# NEpic.net
KiCad netlist of a schematic drawn in Altium Designer
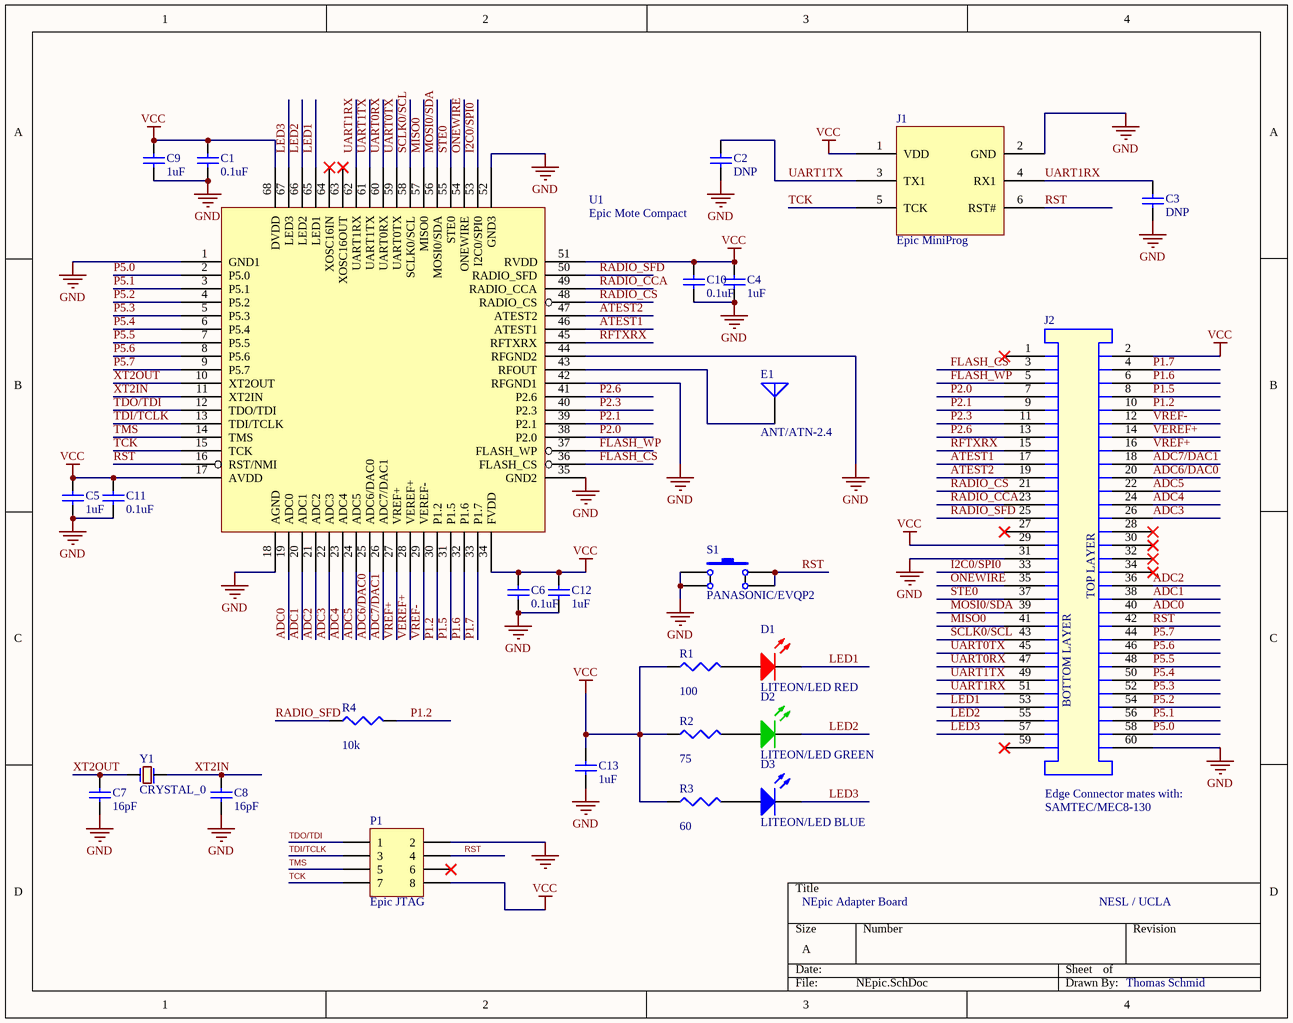
[diagram p0: NEpic.SchDoc]

(export (version "E")
  (design (tool "Eeschema 10.0.6"))
  (components
    (comp (ref "C1")
      (value "0.1uF")
      (footprint "CC1608-0603")
      (description "Capacitor (Semiconductor SIM Model)")
      (fields (field (name "Comment") "Cap") (field (name "PUBLISHER") "Altium Limited"))
      (libsource (lib "Thomas") (part "Cap"))
    )
    (comp (ref "C2")
      (value "DNP")
      (footprint "CC1608-0603")
      (description "Capacitor (Semiconductor SIM Model)")
      (fields (field (name "Comment") "Cap") (field (name "PUBLISHER") "Altium Limited"))
      (libsource (lib "Thomas") (part "Cap"))
    )
    (comp (ref "C3")
      (value "DNP")
      (footprint "CC1608-0603")
      (description "Capacitor (Semiconductor SIM Model)")
      (fields (field (name "Comment") "Cap") (field (name "PUBLISHER") "Altium Limited"))
      (libsource (lib "Thomas") (part "Cap"))
    )
    (comp (ref "C4")
      (value "1uF")
      (footprint "CC1608-0603")
      (description "Capacitor (Semiconductor SIM Model)")
      (fields (field (name "Comment") "Cap") (field (name "PUBLISHER") "Altium Limited"))
      (libsource (lib "Thomas") (part "Cap"))
    )
    (comp (ref "C5")
      (value "1uF")
      (footprint "CC1608-0603")
      (description "Capacitor (Semiconductor SIM Model)")
      (fields (field (name "Comment") "Cap") (field (name "PUBLISHER") "Altium Limited"))
      (libsource (lib "Thomas") (part "Cap"))
    )
    (comp (ref "C6")
      (value "0.1uF")
      (footprint "CC1608-0603")
      (description "Capacitor (Semiconductor SIM Model)")
      (fields (field (name "Comment") "Cap") (field (name "PUBLISHER") "Altium Limited"))
      (libsource (lib "Thomas") (part "Cap"))
    )
    (comp (ref "C7")
      (value "16pF")
      (footprint "CC1608-0603")
      (description "Capacitor (Semiconductor SIM Model)")
      (fields (field (name "Comment") "Cap") (field (name "PUBLISHER") "Altium Limited"))
      (libsource (lib "Thomas") (part "Cap"))
    )
    (comp (ref "C8")
      (value "16pF")
      (footprint "CC1608-0603")
      (description "Capacitor (Semiconductor SIM Model)")
      (fields (field (name "Comment") "Cap") (field (name "PUBLISHER") "Altium Limited"))
      (libsource (lib "Thomas") (part "Cap"))
    )
    (comp (ref "C9")
      (value "1uF")
      (footprint "CC1608-0603")
      (description "Capacitor (Semiconductor SIM Model)")
      (fields (field (name "Comment") "Cap") (field (name "PUBLISHER") "Altium Limited"))
      (libsource (lib "Thomas") (part "Cap"))
    )
    (comp (ref "C10")
      (value "0.1uF")
      (footprint "CC1608-0603")
      (description "Capacitor (Semiconductor SIM Model)")
      (fields (field (name "Comment") "Cap") (field (name "PUBLISHER") "Altium Limited"))
      (libsource (lib "Thomas") (part "Cap"))
    )
    (comp (ref "C11")
      (value "0.1uF")
      (footprint "CC1608-0603")
      (description "Capacitor (Semiconductor SIM Model)")
      (fields (field (name "Comment") "Cap") (field (name "PUBLISHER") "Altium Limited"))
      (libsource (lib "Thomas") (part "Cap"))
    )
    (comp (ref "C12")
      (value "1uF")
      (footprint "CC1608-0603")
      (description "Capacitor (Semiconductor SIM Model)")
      (fields (field (name "Comment") "Cap") (field (name "PUBLISHER") "Altium Limited"))
      (libsource (lib "Thomas") (part "Cap"))
    )
    (comp (ref "C13")
      (value "1uF")
      (footprint "CC1608-0603")
      (description "Capacitor (Semiconductor SIM Model)")
      (fields (field (name "Comment") "Cap") (field (name "PUBLISHER") "Altium Limited"))
      (libsource (lib "Thomas") (part "Cap"))
    )
    (comp (ref "D1")
      (value "LITEON/LED RED")
      (footprint "LITEON/LED/0603")
      (description "LiteOn Red LED 0605 Footprint")
      (fields (field (name "PUBLISHER") "Altium Limited"))
      (libsource (lib "Thomas") (part "LITEON/LED RED"))
    )
    (comp (ref "D2")
      (value "LITEON/LED GREEN")
      (footprint "LITEON/LED/0603")
      (description "LiteOn Green LED 0605 Footprint")
      (fields (field (name "PUBLISHER") "Altium Limited"))
      (libsource (lib "Thomas") (part "LITEON/LED GREEN"))
    )
    (comp (ref "D3")
      (value "LITEON/LED BLUE")
      (footprint "LITEON/LED/0603")
      (description "LiteOn Blue LED 0605 Footprint")
      (fields (field (name "PUBLISHER") "Altium Limited"))
      (libsource (lib "Thomas") (part "LITEON/LED BLUE"))
    )
    (comp (ref "E1")
      (value "ANT/ATN-2.4")
      (footprint "ANT/ANT-2.45-CHPCT-ND")
      (description "ANT/ANT-2.4 Chip Antenna")
      (fields (field (name "PUBLISHER") "Altium Limited"))
      (libsource (lib "Thomas") (part "Antenna"))
    )
    (comp (ref "J1")
      (value "Epic MiniProg")
      (footprint "6-pin 2mm")
      (libsource (lib "Thomas") (part "Epic MiniProg"))
    )
    (comp (ref "J2")
      (value "SAMTEC/MEC8-130")
      (footprint "SAMTEC/MEC8L-130-CARD")
      (description "0.8mm Pitch 60 pin Card Edge Socket")
      (libsource (lib "Thomas") (part "SAMTEC/HSEC8/50"))
    )
    (comp (ref "P1")
      (value "Epic JTAG")
      (footprint "Thomas/Header 2x4 2mm")
      (description "Header, 4-Pin, Dual row")
      (fields (field (name "PUBLISHER") "Altium Limited"))
      (libsource (lib "Miscellaneous Connectors") (part "Header 4X2"))
    )
    (comp (ref "R1")
      (value "100")
      (footprint "CR1608-0603")
      (description "Resistor")
      (fields (field (name "Comment") "Res3") (field (name "PUBLISHER") "Altium Limited"))
      (libsource (lib "Miscellaneous Devices") (part "Res3"))
    )
    (comp (ref "R2")
      (value "75")
      (footprint "CR1608-0603")
      (description "Resistor")
      (fields (field (name "Comment") "Res3") (field (name "PUBLISHER") "Altium Limited"))
      (libsource (lib "Miscellaneous Devices") (part "Res3"))
    )
    (comp (ref "R3")
      (value "60")
      (footprint "CR1608-0603")
      (description "Resistor")
      (fields (field (name "Comment") "Res3") (field (name "PUBLISHER") "Altium Limited"))
      (libsource (lib "Miscellaneous Devices") (part "Res3"))
    )
    (comp (ref "R4")
      (value "10k")
      (footprint "CR1608-0603")
      (description "Resistor")
      (fields (field (name "Comment") "Res3") (field (name "PUBLISHER") "Altium Limited"))
      (libsource (lib "Miscellaneous Devices") (part "Res3"))
    )
    (comp (ref "S1")
      (value "PANASONIC/EVQP2")
      (footprint "PANASONIC/EVQP2")
      (fields (field (name "PUBLISHER") "Altium Limited"))
      (libsource (lib "Thomas") (part "PANASONIC/EVQP2"))
    )
    (comp (ref "U1")
      (value "Epic Mote Compact")
      (footprint "EPIC-Footprint")
      (libsource (lib "Thomas") (part "Epic Mote Compact"))
    )
    (comp (ref "Y1")
      (value "CRYSTAL_0")
      (footprint "FOX/FQ7050B")
      (libsource (lib "Thomas") (part "CRYSTAL_0"))
    )
  )
  (nets
    (net (code "1") (name "/ADC0") (class "Default")
      (node (ref "J2") (pin "40") (pinfunction "40_40") (pintype "passive"))
      (node (ref "U1") (pin "19") (pinfunction "ADC0_19") (pintype "passive"))
    )
    (net (code "2") (name "/ADC1") (class "Default")
      (node (ref "J2") (pin "38") (pinfunction "38_38") (pintype "passive"))
      (node (ref "U1") (pin "20") (pinfunction "ADC1_20") (pintype "passive"))
    )
    (net (code "3") (name "/ADC2") (class "Default")
      (node (ref "J2") (pin "36") (pinfunction "36_36") (pintype "passive"))
      (node (ref "U1") (pin "21") (pinfunction "ADC2_21") (pintype "passive"))
    )
    (net (code "4") (name "/ADC3") (class "Default")
      (node (ref "J2") (pin "26") (pinfunction "26_26") (pintype "passive"))
      (node (ref "U1") (pin "22") (pinfunction "ADC3_22") (pintype "passive"))
    )
    (net (code "5") (name "/ADC4") (class "Default")
      (node (ref "J2") (pin "24") (pinfunction "24_24") (pintype "passive"))
      (node (ref "U1") (pin "23") (pinfunction "ADC4_23") (pintype "passive"))
    )
    (net (code "6") (name "/ADC5") (class "Default")
      (node (ref "J2") (pin "22") (pinfunction "22_22") (pintype "passive"))
      (node (ref "U1") (pin "24") (pinfunction "ADC5_24") (pintype "passive"))
    )
    (net (code "7") (name "/ADC6{slash}DAC0") (class "Default")
      (node (ref "J2") (pin "20") (pinfunction "20_20") (pintype "passive"))
      (node (ref "U1") (pin "25") (pinfunction "ADC6/DAC0_25") (pintype "passive"))
    )
    (net (code "8") (name "/ADC7{slash}DAC1") (class "Default")
      (node (ref "J2") (pin "18") (pinfunction "18_18") (pintype "passive"))
      (node (ref "U1") (pin "26") (pinfunction "ADC7/DAC1_26") (pintype "passive"))
    )
    (net (code "9") (name "/ATEST1") (class "Default")
      (node (ref "J2") (pin "17") (pinfunction "17_17") (pintype "passive"))
      (node (ref "U1") (pin "46") (pinfunction "ATEST1_46") (pintype "passive"))
    )
    (net (code "10") (name "/ATEST2") (class "Default")
      (node (ref "J2") (pin "19") (pinfunction "19_19") (pintype "passive"))
      (node (ref "U1") (pin "47") (pinfunction "ATEST2_47") (pintype "passive"))
    )
    (net (code "11") (name "/FLASH_CS") (class "Default")
      (node (ref "J2") (pin "3") (pinfunction "3_3") (pintype "passive"))
      (node (ref "U1") (pin "36") (pinfunction "FLASH_CS_36") (pintype "passive"))
    )
    (net (code "12") (name "/FLASH_WP") (class "Default")
      (node (ref "J2") (pin "5") (pinfunction "5_5") (pintype "passive"))
      (node (ref "U1") (pin "37") (pinfunction "FLASH_WP_37") (pintype "passive"))
    )
    (net (code "13") (name "/I2C0{slash}SPI0") (class "Default")
      (node (ref "J2") (pin "33") (pinfunction "33_33") (pintype "passive"))
      (node (ref "U1") (pin "53") (pinfunction "I2C0/SPI0_53") (pintype "passive"))
    )
    (net (code "14") (name "/LED1") (class "Default")
      (node (ref "D1") (pin "2") (pinfunction "K_2") (pintype "passive"))
      (node (ref "J2") (pin "53") (pinfunction "53_53") (pintype "passive"))
      (node (ref "U1") (pin "65") (pinfunction "LED1_65") (pintype "passive"))
    )
    (net (code "15") (name "/LED2") (class "Default")
      (node (ref "D2") (pin "2") (pinfunction "K_2") (pintype "passive"))
      (node (ref "J2") (pin "55") (pinfunction "55_55") (pintype "passive"))
      (node (ref "U1") (pin "66") (pinfunction "LED2_66") (pintype "passive"))
    )
    (net (code "16") (name "/LED3") (class "Default")
      (node (ref "D3") (pin "2") (pinfunction "K_2") (pintype "passive"))
      (node (ref "J2") (pin "57") (pinfunction "57_57") (pintype "passive"))
      (node (ref "U1") (pin "67") (pinfunction "LED3_67") (pintype "passive"))
    )
    (net (code "17") (name "/MISO0") (class "Default")
      (node (ref "J2") (pin "41") (pinfunction "41_41") (pintype "passive"))
      (node (ref "U1") (pin "57") (pinfunction "MISO0_57") (pintype "passive"))
    )
    (net (code "18") (name "/MOSI0{slash}SDA") (class "Default")
      (node (ref "J2") (pin "39") (pinfunction "39_39") (pintype "passive"))
      (node (ref "U1") (pin "56") (pinfunction "MOSI0/SDA_56") (pintype "passive"))
    )
    (net (code "19") (name "/ONEWIRE") (class "Default")
      (node (ref "J2") (pin "35") (pinfunction "35_35") (pintype "passive"))
      (node (ref "U1") (pin "54") (pinfunction "ONEWIRE_54") (pintype "passive"))
    )
    (net (code "20") (name "/P1.2") (class "Default")
      (node (ref "J2") (pin "10") (pinfunction "10_10") (pintype "passive"))
      (node (ref "R4") (pin "2") (pinfunction "2_2") (pintype "passive"))
      (node (ref "U1") (pin "30") (pinfunction "P1.2_30") (pintype "passive"))
    )
    (net (code "21") (name "/P1.5") (class "Default")
      (node (ref "J2") (pin "8") (pinfunction "8_8") (pintype "passive"))
      (node (ref "U1") (pin "31") (pinfunction "P1.5_31") (pintype "passive"))
    )
    (net (code "22") (name "/P1.6") (class "Default")
      (node (ref "J2") (pin "6") (pinfunction "6_6") (pintype "passive"))
      (node (ref "U1") (pin "32") (pinfunction "P1.6_32") (pintype "passive"))
    )
    (net (code "23") (name "/P1.7") (class "Default")
      (node (ref "J2") (pin "4") (pinfunction "4_4") (pintype "passive"))
      (node (ref "U1") (pin "33") (pinfunction "P1.7_33") (pintype "passive"))
    )
    (net (code "24") (name "/P2.0") (class "Default")
      (node (ref "J2") (pin "7") (pinfunction "7_7") (pintype "passive"))
      (node (ref "U1") (pin "38") (pinfunction "P2.0_38") (pintype "passive"))
    )
    (net (code "25") (name "/P2.1") (class "Default")
      (node (ref "J2") (pin "9") (pinfunction "9_9") (pintype "passive"))
      (node (ref "U1") (pin "39") (pinfunction "P2.1_39") (pintype "passive"))
    )
    (net (code "26") (name "/P2.3") (class "Default")
      (node (ref "J2") (pin "11") (pinfunction "11_11") (pintype "passive"))
      (node (ref "U1") (pin "40") (pinfunction "P2.3_40") (pintype "passive"))
    )
    (net (code "27") (name "/P2.6") (class "Default")
      (node (ref "J2") (pin "13") (pinfunction "13_13") (pintype "passive"))
      (node (ref "U1") (pin "41") (pinfunction "P2.6_41") (pintype "passive"))
    )
    (net (code "28") (name "/P5.0") (class "Default")
      (node (ref "J2") (pin "58") (pinfunction "58_58") (pintype "passive"))
      (node (ref "U1") (pin "2") (pinfunction "P5.0_2") (pintype "passive"))
    )
    (net (code "29") (name "/P5.1") (class "Default")
      (node (ref "J2") (pin "56") (pinfunction "56_56") (pintype "passive"))
      (node (ref "U1") (pin "3") (pinfunction "P5.1_3") (pintype "passive"))
    )
    (net (code "30") (name "/P5.2") (class "Default")
      (node (ref "J2") (pin "54") (pinfunction "54_54") (pintype "passive"))
      (node (ref "U1") (pin "4") (pinfunction "P5.2_4") (pintype "passive"))
    )
    (net (code "31") (name "/P5.3") (class "Default")
      (node (ref "J2") (pin "52") (pinfunction "52_52") (pintype "passive"))
      (node (ref "U1") (pin "5") (pinfunction "P5.3_5") (pintype "passive"))
    )
    (net (code "32") (name "/P5.4") (class "Default")
      (node (ref "J2") (pin "50") (pinfunction "50_50") (pintype "passive"))
      (node (ref "U1") (pin "6") (pinfunction "P5.4_6") (pintype "passive"))
    )
    (net (code "33") (name "/P5.5") (class "Default")
      (node (ref "J2") (pin "48") (pinfunction "48_48") (pintype "passive"))
      (node (ref "U1") (pin "7") (pinfunction "P5.5_7") (pintype "passive"))
    )
    (net (code "34") (name "/P5.6") (class "Default")
      (node (ref "J2") (pin "46") (pinfunction "46_46") (pintype "passive"))
      (node (ref "U1") (pin "8") (pinfunction "P5.6_8") (pintype "passive"))
    )
    (net (code "35") (name "/P5.7") (class "Default")
      (node (ref "J2") (pin "44") (pinfunction "44_44") (pintype "passive"))
      (node (ref "U1") (pin "9") (pinfunction "P5.7_9") (pintype "passive"))
    )
    (net (code "36") (name "/RADIO_CCA") (class "Default")
      (node (ref "J2") (pin "23") (pinfunction "23_23") (pintype "passive"))
      (node (ref "U1") (pin "49") (pinfunction "RADIO_CCA_49") (pintype "passive"))
    )
    (net (code "37") (name "/RADIO_CS") (class "Default")
      (node (ref "J2") (pin "21") (pinfunction "21_21") (pintype "passive"))
      (node (ref "U1") (pin "48") (pinfunction "RADIO_CS_48") (pintype "passive"))
    )
    (net (code "38") (name "/RADIO_SFD") (class "Default")
      (node (ref "J2") (pin "25") (pinfunction "25_25") (pintype "passive"))
      (node (ref "R4") (pin "1") (pinfunction "1_1") (pintype "passive"))
      (node (ref "U1") (pin "50") (pinfunction "RADIO_SFD_50") (pintype "passive"))
    )
    (net (code "39") (name "/RFTXRX") (class "Default")
      (node (ref "J2") (pin "15") (pinfunction "15_15") (pintype "passive"))
      (node (ref "U1") (pin "45") (pinfunction "RFTXRX_45") (pintype "passive"))
    )
    (net (code "40") (name "/RST") (class "Default")
      (node (ref "J1") (pin "6") (pinfunction "RST#_6") (pintype "passive"))
      (node (ref "J2") (pin "42") (pinfunction "42_42") (pintype "passive"))
      (node (ref "P1") (pin "4") (pinfunction "4_4") (pintype "passive"))
      (node (ref "S1") (pin "2") (pinfunction "2_2") (pintype "passive"))
      (node (ref "S1") (pin "4") (pinfunction "4_4") (pintype "passive"))
      (node (ref "U1") (pin "16") (pinfunction "RST/NMI_16") (pintype "passive"))
    )
    (net (code "41") (name "/SCLK0{slash}SCL") (class "Default")
      (node (ref "J2") (pin "43") (pinfunction "43_43") (pintype "passive"))
      (node (ref "U1") (pin "58") (pinfunction "SCLK0/SCL_58") (pintype "passive"))
    )
    (net (code "42") (name "/STE0") (class "Default")
      (node (ref "J2") (pin "37") (pinfunction "37_37") (pintype "passive"))
      (node (ref "U1") (pin "55") (pinfunction "STE0_55") (pintype "passive"))
    )
    (net (code "43") (name "/TCK") (class "Default")
      (node (ref "J1") (pin "5") (pinfunction "TCK_5") (pintype "passive"))
      (node (ref "P1") (pin "7") (pinfunction "7_7") (pintype "passive"))
      (node (ref "U1") (pin "15") (pinfunction "TCK_15") (pintype "passive"))
    )
    (net (code "44") (name "/TDI{slash}TCLK") (class "Default")
      (node (ref "P1") (pin "3") (pinfunction "3_3") (pintype "passive"))
      (node (ref "U1") (pin "13") (pinfunction "TDI/TCLK_13") (pintype "passive"))
    )
    (net (code "45") (name "/TDO{slash}TDI") (class "Default")
      (node (ref "P1") (pin "1") (pinfunction "1_1") (pintype "passive"))
      (node (ref "U1") (pin "12") (pinfunction "TDO/TDI_12") (pintype "passive"))
    )
    (net (code "46") (name "/TMS") (class "Default")
      (node (ref "P1") (pin "5") (pinfunction "5_5") (pintype "passive"))
      (node (ref "U1") (pin "14") (pinfunction "TMS_14") (pintype "passive"))
    )
    (net (code "47") (name "/UART0RX") (class "Default")
      (node (ref "J2") (pin "47") (pinfunction "47_47") (pintype "passive"))
      (node (ref "U1") (pin "60") (pinfunction "UART0RX_60") (pintype "passive"))
    )
    (net (code "48") (name "/UART0TX") (class "Default")
      (node (ref "J2") (pin "45") (pinfunction "45_45") (pintype "passive"))
      (node (ref "U1") (pin "59") (pinfunction "UART0TX_59") (pintype "passive"))
    )
    (net (code "49") (name "/UART1RX") (class "Default")
      (node (ref "C3") (pin "2") (pinfunction "2_2") (pintype "passive"))
      (node (ref "J1") (pin "4") (pinfunction "RX1_4") (pintype "passive"))
      (node (ref "J2") (pin "51") (pinfunction "51_51") (pintype "passive"))
      (node (ref "U1") (pin "62") (pinfunction "UART1RX_62") (pintype "passive"))
    )
    (net (code "50") (name "/UART1TX") (class "Default")
      (node (ref "C2") (pin "2") (pinfunction "2_2") (pintype "passive"))
      (node (ref "J1") (pin "3") (pinfunction "TX1_3") (pintype "passive"))
      (node (ref "J2") (pin "49") (pinfunction "49_49") (pintype "passive"))
      (node (ref "U1") (pin "61") (pinfunction "UART1TX_61") (pintype "passive"))
    )
    (net (code "51") (name "/VEREF+") (class "Default")
      (node (ref "J2") (pin "14") (pinfunction "14_14") (pintype "passive"))
      (node (ref "U1") (pin "28") (pinfunction "VEREF+_28") (pintype "passive"))
    )
    (net (code "52") (name "/VREF+") (class "Default")
      (node (ref "J2") (pin "16") (pinfunction "16_16") (pintype "passive"))
      (node (ref "U1") (pin "27") (pinfunction "VREF+_27") (pintype "passive"))
    )
    (net (code "53") (name "/VREF-") (class "Default")
      (node (ref "J2") (pin "12") (pinfunction "12_12") (pintype "passive"))
      (node (ref "U1") (pin "29") (pinfunction "VEREF-_29") (pintype "passive"))
    )
    (net (code "54") (name "/XT2IN") (class "Default")
      (node (ref "C8") (pin "2") (pinfunction "2_2") (pintype "passive"))
      (node (ref "U1") (pin "11") (pinfunction "XT2IN_11") (pintype "passive"))
      (node (ref "Y1") (pin "2") (pinfunction "2_2") (pintype "passive"))
    )
    (net (code "55") (name "/XT2OUT") (class "Default")
      (node (ref "C7") (pin "2") (pinfunction "2_2") (pintype "passive"))
      (node (ref "U1") (pin "10") (pinfunction "XT2OUT_10") (pintype "passive"))
      (node (ref "Y1") (pin "1") (pinfunction "1_1") (pintype "passive"))
    )
    (net (code "56") (name "GND") (class "Default")
      (node (ref "C1") (pin "1") (pinfunction "1_1") (pintype "passive"))
      (node (ref "C10") (pin "1") (pinfunction "1_1") (pintype "passive"))
      (node (ref "C11") (pin "1") (pinfunction "1_1") (pintype "passive"))
      (node (ref "C12") (pin "1") (pinfunction "1_1") (pintype "passive"))
      (node (ref "C13") (pin "1") (pinfunction "1_1") (pintype "passive"))
      (node (ref "C2") (pin "1") (pinfunction "1_1") (pintype "passive"))
      (node (ref "C3") (pin "1") (pinfunction "1_1") (pintype "passive"))
      (node (ref "C4") (pin "1") (pinfunction "1_1") (pintype "passive"))
      (node (ref "C5") (pin "1") (pinfunction "1_1") (pintype "passive"))
      (node (ref "C6") (pin "1") (pinfunction "1_1") (pintype "passive"))
      (node (ref "C7") (pin "1") (pinfunction "1_1") (pintype "passive"))
      (node (ref "C8") (pin "1") (pinfunction "1_1") (pintype "passive"))
      (node (ref "C9") (pin "1") (pinfunction "1_1") (pintype "passive"))
      (node (ref "J1") (pin "2") (pinfunction "GND_2") (pintype "passive"))
      (node (ref "J2") (pin "31") (pinfunction "31_31") (pintype "passive"))
      (node (ref "J2") (pin "60") (pinfunction "60_60") (pintype "passive"))
      (node (ref "P1") (pin "2") (pinfunction "2_2") (pintype "passive"))
      (node (ref "S1") (pin "1") (pinfunction "1_1") (pintype "passive"))
      (node (ref "S1") (pin "3") (pinfunction "3_3") (pintype "passive"))
      (node (ref "U1") (pin "1") (pinfunction "GND1_1") (pintype "passive"))
      (node (ref "U1") (pin "18") (pinfunction "AGND_18") (pintype "passive"))
      (node (ref "U1") (pin "35") (pinfunction "GND2_35") (pintype "passive"))
      (node (ref "U1") (pin "42") (pinfunction "RFGND1_42") (pintype "passive"))
      (node (ref "U1") (pin "44") (pinfunction "RFGND2_44") (pintype "passive"))
      (node (ref "U1") (pin "52") (pinfunction "GND3_52") (pintype "passive"))
    )
    (net (code "57") (name "Net-(D1-A)") (class "Default")
      (node (ref "D1") (pin "1") (pinfunction "A_1") (pintype "passive"))
      (node (ref "R1") (pin "2") (pinfunction "2_2") (pintype "passive"))
    )
    (net (code "58") (name "Net-(D2-A)") (class "Default")
      (node (ref "D2") (pin "1") (pinfunction "A_1") (pintype "passive"))
      (node (ref "R2") (pin "2") (pinfunction "2_2") (pintype "passive"))
    )
    (net (code "59") (name "Net-(D3-A)") (class "Default")
      (node (ref "D3") (pin "1") (pinfunction "A_1") (pintype "passive"))
      (node (ref "R3") (pin "2") (pinfunction "2_2") (pintype "passive"))
    )
    (net (code "60") (name "Net-(E1-A)") (class "Default")
      (node (ref "E1") (pin "1") (pinfunction "A_1") (pintype "passive"))
      (node (ref "U1") (pin "43") (pinfunction "RFOUT_43") (pintype "passive"))
    )
    (net (code "61") (name "VCC") (class "Default")
      (node (ref "C1") (pin "2") (pinfunction "2_2") (pintype "passive"))
      (node (ref "C10") (pin "2") (pinfunction "2_2") (pintype "passive"))
      (node (ref "C11") (pin "2") (pinfunction "2_2") (pintype "passive"))
      (node (ref "C12") (pin "2") (pinfunction "2_2") (pintype "passive"))
      (node (ref "C13") (pin "2") (pinfunction "2_2") (pintype "passive"))
      (node (ref "C4") (pin "2") (pinfunction "2_2") (pintype "passive"))
      (node (ref "C5") (pin "2") (pinfunction "2_2") (pintype "passive"))
      (node (ref "C6") (pin "2") (pinfunction "2_2") (pintype "passive"))
      (node (ref "C9") (pin "2") (pinfunction "2_2") (pintype "passive"))
      (node (ref "J1") (pin "1") (pinfunction "VDD_1") (pintype "passive"))
      (node (ref "J2") (pin "2") (pinfunction "2_2") (pintype "passive"))
      (node (ref "J2") (pin "29") (pinfunction "29_29") (pintype "passive"))
      (node (ref "P1") (pin "8") (pinfunction "8_8") (pintype "passive"))
      (node (ref "R1") (pin "1") (pinfunction "1_1") (pintype "passive"))
      (node (ref "R2") (pin "1") (pinfunction "1_1") (pintype "passive"))
      (node (ref "R3") (pin "1") (pinfunction "1_1") (pintype "passive"))
      (node (ref "U1") (pin "17") (pinfunction "AVDD_17") (pintype "passive"))
      (node (ref "U1") (pin "34") (pinfunction "FVDD_34") (pintype "passive"))
      (node (ref "U1") (pin "51") (pinfunction "RVDD_51") (pintype "passive"))
      (node (ref "U1") (pin "68") (pinfunction "DVDD_68") (pintype "passive"))
    )
    (net (code "62") (name "unconnected-(J2-Pad1)") (class "Default")
      (node (ref "J2") (pin "1") (pinfunction "1_1") (pintype "passive+no_connect"))
    )
    (net (code "63") (name "unconnected-(J2-Pad27)") (class "Default")
      (node (ref "J2") (pin "27") (pinfunction "27_27") (pintype "passive+no_connect"))
    )
    (net (code "64") (name "unconnected-(J2-Pad28)") (class "Default")
      (node (ref "J2") (pin "28") (pinfunction "28_28") (pintype "passive+no_connect"))
    )
    (net (code "65") (name "unconnected-(J2-Pad30)") (class "Default")
      (node (ref "J2") (pin "30") (pinfunction "30_30") (pintype "passive+no_connect"))
    )
    (net (code "66") (name "unconnected-(J2-Pad32)") (class "Default")
      (node (ref "J2") (pin "32") (pinfunction "32_32") (pintype "passive+no_connect"))
    )
    (net (code "67") (name "unconnected-(J2-Pad34)") (class "Default")
      (node (ref "J2") (pin "34") (pinfunction "34_34") (pintype "passive+no_connect"))
    )
    (net (code "68") (name "unconnected-(J2-Pad59)") (class "Default")
      (node (ref "J2") (pin "59") (pinfunction "59_59") (pintype "passive+no_connect"))
    )
    (net (code "69") (name "unconnected-(P1-Pad6)") (class "Default")
      (node (ref "P1") (pin "6") (pinfunction "6_6") (pintype "passive+no_connect"))
    )
    (net (code "70") (name "unconnected-(U1-XOSC16IN-Pad64)") (class "Default")
      (node (ref "U1") (pin "64") (pinfunction "XOSC16IN_64") (pintype "passive+no_connect"))
    )
    (net (code "71") (name "unconnected-(U1-XOSC16OUT-Pad63)") (class "Default")
      (node (ref "U1") (pin "63") (pinfunction "XOSC16OUT_63") (pintype "passive+no_connect"))
    )
  )
)
